# CONNECTEUR_2.net
KiCad netlist of a schematic drawn in Altium Designer
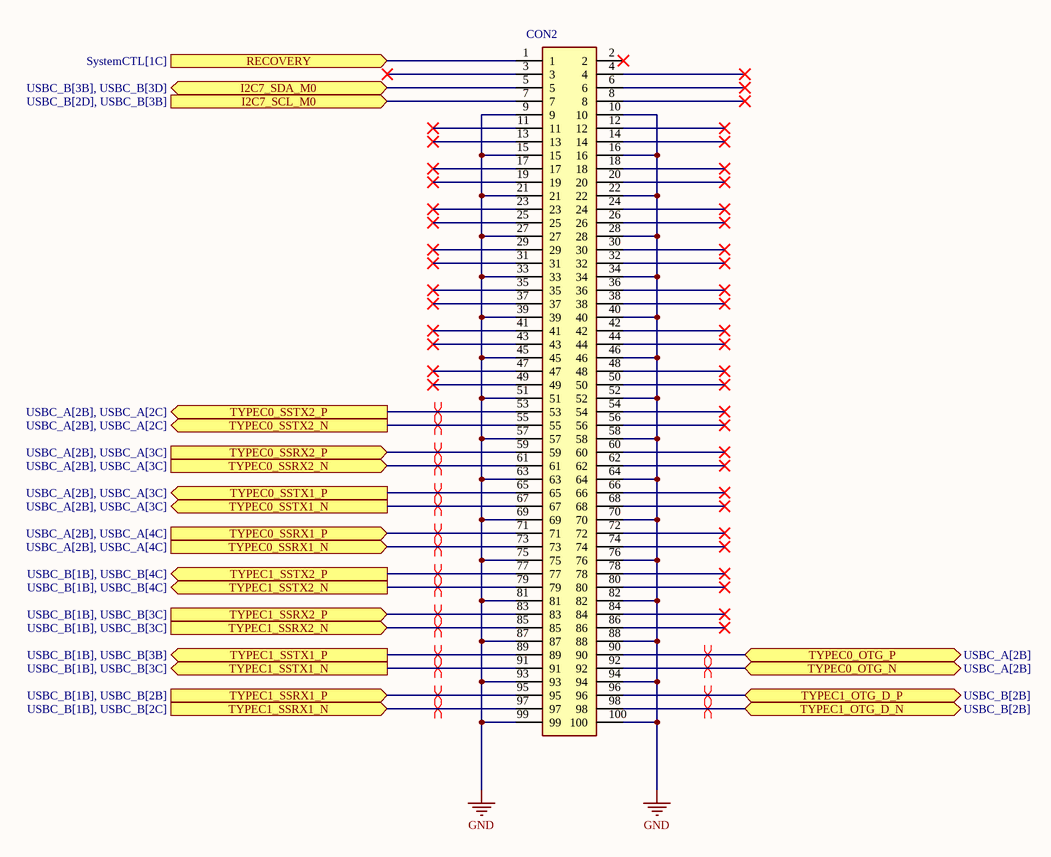
[diagram p0: CONNECTEUR_2.SchDoc]

(export (version "E")
  (design (tool "Eeschema 10.0.6"))
  (components
    (comp (ref "CON2")
      (value "DF40HC")
      (footprint "DF40HC30100DS04V51_MOD")
      (description "Stacking Board Connector, DF40 Series, Receptacle, 0.4 mm, 100, Surface Mount, G")
      (fields
        (field (name "MANUFACTURER_PART_NUMBER") "DF40HC(3.0)-100DS-0.4V(51")
        (field (name "MOUSER PART NUMBER") "798-DF40HC30100DS451")
      )
      (libsource (lib "DARKYDEN") (part "DF40HC(3.0)-100DS-0.4V(51)"))
    )
  )
  (nets
    (net (code "1") (name "/I2C7_SCL_M0") (class "Default")
      (node (ref "CON2") (pin "7") (pinfunction "7_7") (pintype "passive"))
    )
    (net (code "2") (name "/I2C7_SDA_M0") (class "Default")
      (node (ref "CON2") (pin "5") (pinfunction "5_5") (pintype "passive"))
    )
    (net (code "3") (name "/RECOVERY") (class "Default")
      (node (ref "CON2") (pin "1") (pinfunction "1_1") (pintype "passive"))
    )
    (net (code "4") (name "/TYPEC0_OTG_N") (class "Default")
      (node (ref "CON2") (pin "92") (pinfunction "92_92") (pintype "passive"))
    )
    (net (code "5") (name "/TYPEC0_OTG_P") (class "Default")
      (node (ref "CON2") (pin "90") (pinfunction "90_90") (pintype "passive"))
    )
    (net (code "6") (name "/TYPEC0_SSRX1_N") (class "Default")
      (node (ref "CON2") (pin "73") (pinfunction "73_73") (pintype "passive"))
    )
    (net (code "7") (name "/TYPEC0_SSRX1_P") (class "Default")
      (node (ref "CON2") (pin "71") (pinfunction "71_71") (pintype "passive"))
    )
    (net (code "8") (name "/TYPEC0_SSRX2_N") (class "Default")
      (node (ref "CON2") (pin "61") (pinfunction "61_61") (pintype "passive"))
    )
    (net (code "9") (name "/TYPEC0_SSRX2_P") (class "Default")
      (node (ref "CON2") (pin "59") (pinfunction "59_59") (pintype "passive"))
    )
    (net (code "10") (name "/TYPEC0_SSTX1_N") (class "Default")
      (node (ref "CON2") (pin "67") (pinfunction "67_67") (pintype "passive"))
    )
    (net (code "11") (name "/TYPEC0_SSTX1_P") (class "Default")
      (node (ref "CON2") (pin "65") (pinfunction "65_65") (pintype "passive"))
    )
    (net (code "12") (name "/TYPEC0_SSTX2_N") (class "Default")
      (node (ref "CON2") (pin "55") (pinfunction "55_55") (pintype "passive"))
    )
    (net (code "13") (name "/TYPEC0_SSTX2_P") (class "Default")
      (node (ref "CON2") (pin "53") (pinfunction "53_53") (pintype "passive"))
    )
    (net (code "14") (name "/TYPEC1_OTG_D_N") (class "Default")
      (node (ref "CON2") (pin "98") (pinfunction "98_98") (pintype "passive"))
    )
    (net (code "15") (name "/TYPEC1_OTG_D_P") (class "Default")
      (node (ref "CON2") (pin "96") (pinfunction "96_96") (pintype "passive"))
    )
    (net (code "16") (name "/TYPEC1_SSRX1_N") (class "Default")
      (node (ref "CON2") (pin "97") (pinfunction "97_97") (pintype "passive"))
    )
    (net (code "17") (name "/TYPEC1_SSRX1_P") (class "Default")
      (node (ref "CON2") (pin "95") (pinfunction "95_95") (pintype "passive"))
    )
    (net (code "18") (name "/TYPEC1_SSRX2_N") (class "Default")
      (node (ref "CON2") (pin "85") (pinfunction "85_85") (pintype "passive"))
    )
    (net (code "19") (name "/TYPEC1_SSRX2_P") (class "Default")
      (node (ref "CON2") (pin "83") (pinfunction "83_83") (pintype "passive"))
    )
    (net (code "20") (name "/TYPEC1_SSTX1_N") (class "Default")
      (node (ref "CON2") (pin "91") (pinfunction "91_91") (pintype "passive"))
    )
    (net (code "21") (name "/TYPEC1_SSTX1_P") (class "Default")
      (node (ref "CON2") (pin "89") (pinfunction "89_89") (pintype "passive"))
    )
    (net (code "22") (name "/TYPEC1_SSTX2_N") (class "Default")
      (node (ref "CON2") (pin "79") (pinfunction "79_79") (pintype "passive"))
    )
    (net (code "23") (name "/TYPEC1_SSTX2_P") (class "Default")
      (node (ref "CON2") (pin "77") (pinfunction "77_77") (pintype "passive"))
    )
    (net (code "24") (name "GND") (class "Default")
      (node (ref "CON2") (pin "10") (pinfunction "10_10") (pintype "passive"))
      (node (ref "CON2") (pin "100") (pinfunction "100_100") (pintype "passive"))
      (node (ref "CON2") (pin "15") (pinfunction "15_15") (pintype "passive"))
      (node (ref "CON2") (pin "16") (pinfunction "16_16") (pintype "passive"))
      (node (ref "CON2") (pin "21") (pinfunction "21_21") (pintype "passive"))
      (node (ref "CON2") (pin "22") (pinfunction "22_22") (pintype "passive"))
      (node (ref "CON2") (pin "27") (pinfunction "27_27") (pintype "passive"))
      (node (ref "CON2") (pin "28") (pinfunction "28_28") (pintype "passive"))
      (node (ref "CON2") (pin "33") (pinfunction "33_33") (pintype "passive"))
      (node (ref "CON2") (pin "34") (pinfunction "34_34") (pintype "passive"))
      (node (ref "CON2") (pin "39") (pinfunction "39_39") (pintype "passive"))
      (node (ref "CON2") (pin "40") (pinfunction "40_40") (pintype "passive"))
      (node (ref "CON2") (pin "45") (pinfunction "45_45") (pintype "passive"))
      (node (ref "CON2") (pin "46") (pinfunction "46_46") (pintype "passive"))
      (node (ref "CON2") (pin "51") (pinfunction "51_51") (pintype "passive"))
      (node (ref "CON2") (pin "52") (pinfunction "52_52") (pintype "passive"))
      (node (ref "CON2") (pin "57") (pinfunction "57_57") (pintype "passive"))
      (node (ref "CON2") (pin "58") (pinfunction "58_58") (pintype "passive"))
      (node (ref "CON2") (pin "63") (pinfunction "63_63") (pintype "passive"))
      (node (ref "CON2") (pin "64") (pinfunction "64_64") (pintype "passive"))
      (node (ref "CON2") (pin "69") (pinfunction "69_69") (pintype "passive"))
      (node (ref "CON2") (pin "70") (pinfunction "70_70") (pintype "passive"))
      (node (ref "CON2") (pin "75") (pinfunction "75_75") (pintype "passive"))
      (node (ref "CON2") (pin "76") (pinfunction "76_76") (pintype "passive"))
      (node (ref "CON2") (pin "81") (pinfunction "81_81") (pintype "passive"))
      (node (ref "CON2") (pin "82") (pinfunction "82_82") (pintype "passive"))
      (node (ref "CON2") (pin "87") (pinfunction "87_87") (pintype "passive"))
      (node (ref "CON2") (pin "88") (pinfunction "88_88") (pintype "passive"))
      (node (ref "CON2") (pin "9") (pinfunction "9_9") (pintype "passive"))
      (node (ref "CON2") (pin "93") (pinfunction "93_93") (pintype "passive"))
      (node (ref "CON2") (pin "94") (pinfunction "94_94") (pintype "passive"))
      (node (ref "CON2") (pin "99") (pinfunction "99_99") (pintype "passive"))
    )
    (net (code "25") (name "unconnected-(CON2-Pad2)") (class "Default")
      (node (ref "CON2") (pin "2") (pinfunction "2_2") (pintype "passive+no_connect"))
    )
    (net (code "26") (name "unconnected-(CON2-Pad3)") (class "Default")
      (node (ref "CON2") (pin "3") (pinfunction "3_3") (pintype "passive+no_connect"))
    )
    (net (code "27") (name "unconnected-(CON2-Pad4)") (class "Default")
      (node (ref "CON2") (pin "4") (pinfunction "4_4") (pintype "passive+no_connect"))
    )
    (net (code "28") (name "unconnected-(CON2-Pad6)") (class "Default")
      (node (ref "CON2") (pin "6") (pinfunction "6_6") (pintype "passive+no_connect"))
    )
    (net (code "29") (name "unconnected-(CON2-Pad8)") (class "Default")
      (node (ref "CON2") (pin "8") (pinfunction "8_8") (pintype "passive+no_connect"))
    )
    (net (code "30") (name "unconnected-(CON2-Pad11)") (class "Default")
      (node (ref "CON2") (pin "11") (pinfunction "11_11") (pintype "passive+no_connect"))
    )
    (net (code "31") (name "unconnected-(CON2-Pad12)") (class "Default")
      (node (ref "CON2") (pin "12") (pinfunction "12_12") (pintype "passive+no_connect"))
    )
    (net (code "32") (name "unconnected-(CON2-Pad13)") (class "Default")
      (node (ref "CON2") (pin "13") (pinfunction "13_13") (pintype "passive+no_connect"))
    )
    (net (code "33") (name "unconnected-(CON2-Pad14)") (class "Default")
      (node (ref "CON2") (pin "14") (pinfunction "14_14") (pintype "passive+no_connect"))
    )
    (net (code "34") (name "unconnected-(CON2-Pad17)") (class "Default")
      (node (ref "CON2") (pin "17") (pinfunction "17_17") (pintype "passive+no_connect"))
    )
    (net (code "35") (name "unconnected-(CON2-Pad18)") (class "Default")
      (node (ref "CON2") (pin "18") (pinfunction "18_18") (pintype "passive+no_connect"))
    )
    (net (code "36") (name "unconnected-(CON2-Pad19)") (class "Default")
      (node (ref "CON2") (pin "19") (pinfunction "19_19") (pintype "passive+no_connect"))
    )
    (net (code "37") (name "unconnected-(CON2-Pad20)") (class "Default")
      (node (ref "CON2") (pin "20") (pinfunction "20_20") (pintype "passive+no_connect"))
    )
    (net (code "38") (name "unconnected-(CON2-Pad23)") (class "Default")
      (node (ref "CON2") (pin "23") (pinfunction "23_23") (pintype "passive+no_connect"))
    )
    (net (code "39") (name "unconnected-(CON2-Pad24)") (class "Default")
      (node (ref "CON2") (pin "24") (pinfunction "24_24") (pintype "passive+no_connect"))
    )
    (net (code "40") (name "unconnected-(CON2-Pad25)") (class "Default")
      (node (ref "CON2") (pin "25") (pinfunction "25_25") (pintype "passive+no_connect"))
    )
    (net (code "41") (name "unconnected-(CON2-Pad26)") (class "Default")
      (node (ref "CON2") (pin "26") (pinfunction "26_26") (pintype "passive+no_connect"))
    )
    (net (code "42") (name "unconnected-(CON2-Pad29)") (class "Default")
      (node (ref "CON2") (pin "29") (pinfunction "29_29") (pintype "passive+no_connect"))
    )
    (net (code "43") (name "unconnected-(CON2-Pad30)") (class "Default")
      (node (ref "CON2") (pin "30") (pinfunction "30_30") (pintype "passive+no_connect"))
    )
    (net (code "44") (name "unconnected-(CON2-Pad31)") (class "Default")
      (node (ref "CON2") (pin "31") (pinfunction "31_31") (pintype "passive+no_connect"))
    )
    (net (code "45") (name "unconnected-(CON2-Pad32)") (class "Default")
      (node (ref "CON2") (pin "32") (pinfunction "32_32") (pintype "passive+no_connect"))
    )
    (net (code "46") (name "unconnected-(CON2-Pad35)") (class "Default")
      (node (ref "CON2") (pin "35") (pinfunction "35_35") (pintype "passive+no_connect"))
    )
    (net (code "47") (name "unconnected-(CON2-Pad36)") (class "Default")
      (node (ref "CON2") (pin "36") (pinfunction "36_36") (pintype "passive+no_connect"))
    )
    (net (code "48") (name "unconnected-(CON2-Pad37)") (class "Default")
      (node (ref "CON2") (pin "37") (pinfunction "37_37") (pintype "passive+no_connect"))
    )
    (net (code "49") (name "unconnected-(CON2-Pad38)") (class "Default")
      (node (ref "CON2") (pin "38") (pinfunction "38_38") (pintype "passive+no_connect"))
    )
    (net (code "50") (name "unconnected-(CON2-Pad41)") (class "Default")
      (node (ref "CON2") (pin "41") (pinfunction "41_41") (pintype "passive+no_connect"))
    )
    (net (code "51") (name "unconnected-(CON2-Pad42)") (class "Default")
      (node (ref "CON2") (pin "42") (pinfunction "42_42") (pintype "passive+no_connect"))
    )
    (net (code "52") (name "unconnected-(CON2-Pad43)") (class "Default")
      (node (ref "CON2") (pin "43") (pinfunction "43_43") (pintype "passive+no_connect"))
    )
    (net (code "53") (name "unconnected-(CON2-Pad44)") (class "Default")
      (node (ref "CON2") (pin "44") (pinfunction "44_44") (pintype "passive+no_connect"))
    )
    (net (code "54") (name "unconnected-(CON2-Pad47)") (class "Default")
      (node (ref "CON2") (pin "47") (pinfunction "47_47") (pintype "passive+no_connect"))
    )
    (net (code "55") (name "unconnected-(CON2-Pad48)") (class "Default")
      (node (ref "CON2") (pin "48") (pinfunction "48_48") (pintype "passive+no_connect"))
    )
    (net (code "56") (name "unconnected-(CON2-Pad49)") (class "Default")
      (node (ref "CON2") (pin "49") (pinfunction "49_49") (pintype "passive+no_connect"))
    )
    (net (code "57") (name "unconnected-(CON2-Pad50)") (class "Default")
      (node (ref "CON2") (pin "50") (pinfunction "50_50") (pintype "passive+no_connect"))
    )
    (net (code "58") (name "unconnected-(CON2-Pad54)") (class "Default")
      (node (ref "CON2") (pin "54") (pinfunction "54_54") (pintype "passive+no_connect"))
    )
    (net (code "59") (name "unconnected-(CON2-Pad56)") (class "Default")
      (node (ref "CON2") (pin "56") (pinfunction "56_56") (pintype "passive+no_connect"))
    )
    (net (code "60") (name "unconnected-(CON2-Pad60)") (class "Default")
      (node (ref "CON2") (pin "60") (pinfunction "60_60") (pintype "passive+no_connect"))
    )
    (net (code "61") (name "unconnected-(CON2-Pad62)") (class "Default")
      (node (ref "CON2") (pin "62") (pinfunction "62_62") (pintype "passive+no_connect"))
    )
    (net (code "62") (name "unconnected-(CON2-Pad66)") (class "Default")
      (node (ref "CON2") (pin "66") (pinfunction "66_66") (pintype "passive+no_connect"))
    )
    (net (code "63") (name "unconnected-(CON2-Pad68)") (class "Default")
      (node (ref "CON2") (pin "68") (pinfunction "68_68") (pintype "passive+no_connect"))
    )
    (net (code "64") (name "unconnected-(CON2-Pad72)") (class "Default")
      (node (ref "CON2") (pin "72") (pinfunction "72_72") (pintype "passive+no_connect"))
    )
    (net (code "65") (name "unconnected-(CON2-Pad74)") (class "Default")
      (node (ref "CON2") (pin "74") (pinfunction "74_74") (pintype "passive+no_connect"))
    )
    (net (code "66") (name "unconnected-(CON2-Pad78)") (class "Default")
      (node (ref "CON2") (pin "78") (pinfunction "78_78") (pintype "passive+no_connect"))
    )
    (net (code "67") (name "unconnected-(CON2-Pad80)") (class "Default")
      (node (ref "CON2") (pin "80") (pinfunction "80_80") (pintype "passive+no_connect"))
    )
    (net (code "68") (name "unconnected-(CON2-Pad84)") (class "Default")
      (node (ref "CON2") (pin "84") (pinfunction "84_84") (pintype "passive+no_connect"))
    )
    (net (code "69") (name "unconnected-(CON2-Pad86)") (class "Default")
      (node (ref "CON2") (pin "86") (pinfunction "86_86") (pintype "passive+no_connect"))
    )
  )
)
